# 02-Power.net
KiCad netlist of a schematic drawn in Altium Designer
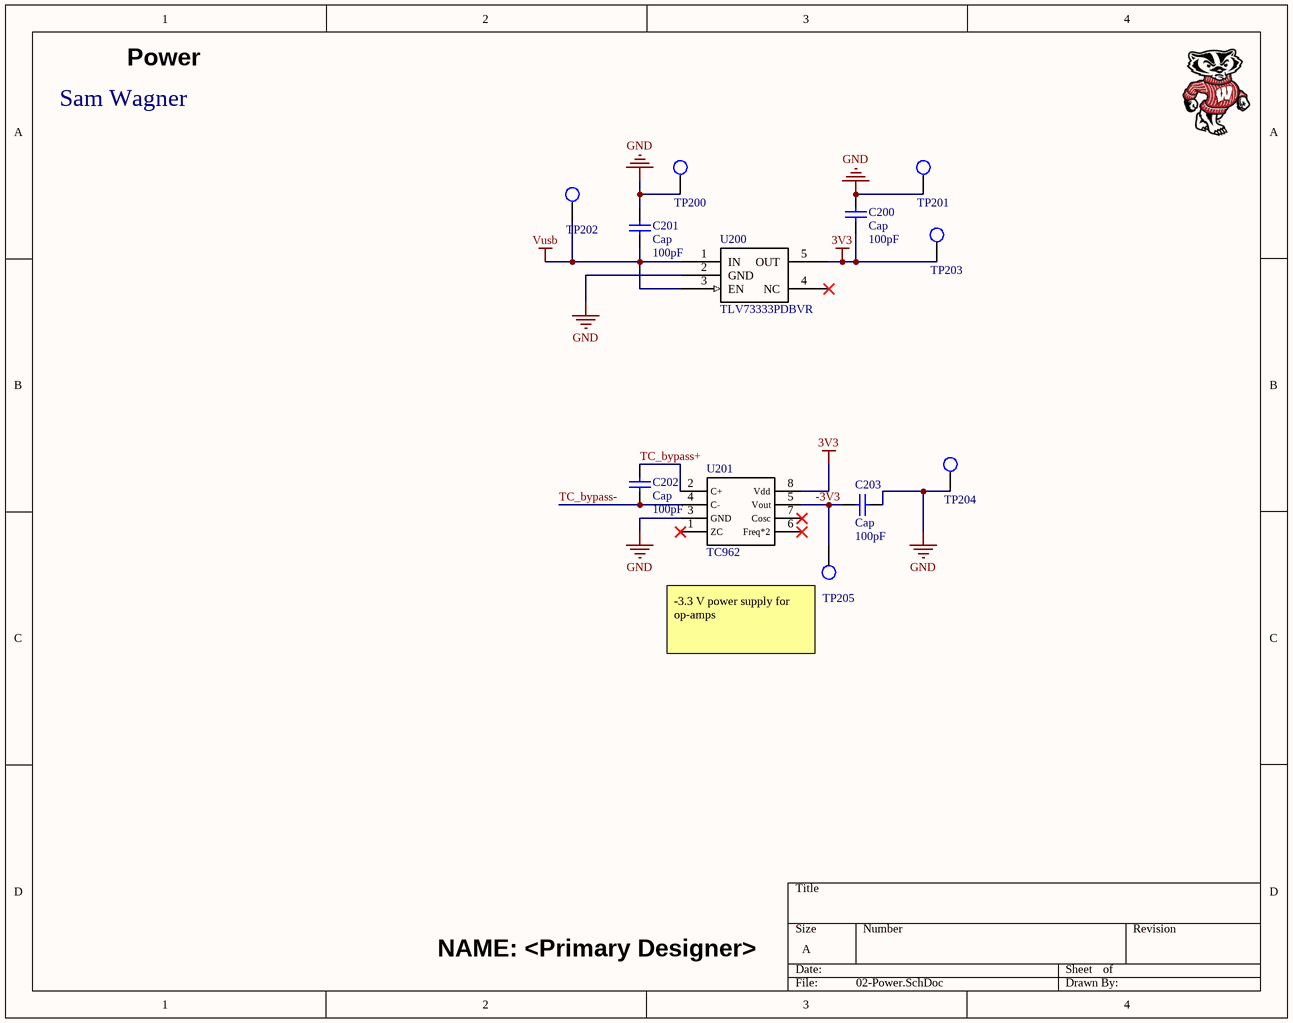
[diagram p0: 02-Power.SchDoc]

(export (version "E")
  (design (tool "Eeschema 10.0.6"))
  (components
    (comp (ref "C200")
      (value "Cap")
      (footprint "RAD-0.3")
      (description "Capacitor")
      (fields (field (name "ALTIUM_VALUE") "100pF") (field (name "PUBLISHER") "Altium Limited"))
      (libsource (lib "Miscellaneous Devices") (part "Cap"))
    )
    (comp (ref "C201")
      (value "Cap")
      (footprint "RAD-0.3")
      (description "Capacitor")
      (fields (field (name "ALTIUM_VALUE") "100pF") (field (name "PUBLISHER") "Altium Limited"))
      (libsource (lib "Miscellaneous Devices") (part "Cap"))
    )
    (comp (ref "C202")
      (value "Cap")
      (footprint "RAD-0.3")
      (description "Capacitor")
      (fields (field (name "ALTIUM_VALUE") "100pF") (field (name "PUBLISHER") "Altium Limited"))
      (libsource (lib "Miscellaneous Devices") (part "Cap"))
    )
    (comp (ref "C203")
      (value "Cap")
      (footprint "RAD-0.3")
      (description "Capacitor")
      (fields (field (name "ALTIUM_VALUE") "100pF") (field (name "PUBLISHER") "Altium Limited"))
      (libsource (lib "Miscellaneous Devices") (part "Cap"))
    )
    (comp (ref "TP200")
      (value "TP_1206")
      (footprint "TP-SMC-1206")
      (description "Test Point SMD 1206")
      (fields
        (field (name "MANUFACTURER") "TE Connectivity (Tyco Electronics)")
        (field (name "MANUFACTURER PART NUMBER") "1625854-1")
      )
      (libsource (lib "ece315-S20") (part "TP_1206"))
    )
    (comp (ref "TP201")
      (value "TP_1206")
      (footprint "TP-SMC-1206")
      (description "Test Point SMD 1206")
      (fields
        (field (name "MANUFACTURER") "TE Connectivity (Tyco Electronics)")
        (field (name "MANUFACTURER PART NUMBER") "1625854-1")
      )
      (libsource (lib "ece315-S20") (part "TP_1206"))
    )
    (comp (ref "TP202")
      (value "TP_1206")
      (footprint "TP-SMC-1206")
      (description "Test Point SMD 1206")
      (fields
        (field (name "MANUFACTURER") "TE Connectivity (Tyco Electronics)")
        (field (name "MANUFACTURER PART NUMBER") "1625854-1")
      )
      (libsource (lib "ece315-S20") (part "TP_1206"))
    )
    (comp (ref "TP203")
      (value "TP_1206")
      (footprint "TP-SMC-1206")
      (description "Test Point SMD 1206")
      (fields
        (field (name "MANUFACTURER") "TE Connectivity (Tyco Electronics)")
        (field (name "MANUFACTURER PART NUMBER") "1625854-1")
      )
      (libsource (lib "ece315-S20") (part "TP_1206"))
    )
    (comp (ref "TP204")
      (value "TP_1206")
      (footprint "TP-SMC-1206")
      (description "Test Point SMD 1206")
      (fields
        (field (name "MANUFACTURER") "TE Connectivity (Tyco Electronics)")
        (field (name "MANUFACTURER PART NUMBER") "1625854-1")
      )
      (libsource (lib "ece315-S20") (part "TP_1206"))
    )
    (comp (ref "TP205")
      (value "TP_1206")
      (footprint "TP-SMC-1206")
      (description "Test Point SMD 1206")
      (fields
        (field (name "MANUFACTURER") "TE Connectivity (Tyco Electronics)")
        (field (name "MANUFACTURER PART NUMBER") "1625854-1")
      )
      (libsource (lib "ece315-S20") (part "TP_1206"))
    )
    (comp (ref "U200")
      (value "IC-TLV733P")
      (footprint "IC_TLV73333")
      (description "IC REG LINEAR 3.3V 300MA SOT23-5")
      (fields
        (field (name "MANUFACTURER") "Texas Instruments")
        (field (name "MANUFACTOR PART NUMBER") "TLV73333PDBVR")
        (field (name "MANUFACTURER PART NUMBER") "TLV73333PDBVR")
      )
      (libsource (lib "ece315-S20") (part "IC-TLV733P"))
    )
    (comp (ref "U201")
      (value "TC962")
      (footprint "DIP8")
      (libsource (lib "Final_Project_Power") (part "TC962"))
    )
  )
  (nets
    (net (code "1") (name "/-3V3") (class "Default")
      (node (ref "C203") (pin "2") (pinfunction "2_2") (pintype "passive"))
      (node (ref "TP205") (pin "1") (pintype "passive"))
      (node (ref "U201") (pin "5") (pinfunction "Vout_5") (pintype "passive"))
    )
    (net (code "2") (name "/TC_bypass+") (class "Default")
      (node (ref "C202") (pin "1") (pinfunction "1_1") (pintype "passive"))
      (node (ref "U201") (pin "2") (pinfunction "C+_2") (pintype "passive"))
    )
    (net (code "3") (name "/TC_bypass-") (class "Default")
      (node (ref "C202") (pin "2") (pinfunction "2_2") (pintype "passive"))
      (node (ref "U201") (pin "4") (pinfunction "C-_4") (pintype "passive"))
    )
    (net (code "4") (name "3V3") (class "Default")
      (node (ref "C200") (pin "2") (pinfunction "2_2") (pintype "passive"))
      (node (ref "TP203") (pin "1") (pintype "passive"))
      (node (ref "U200") (pin "5") (pinfunction "OUT_5") (pintype "power_in"))
      (node (ref "U201") (pin "8") (pinfunction "Vdd_8") (pintype "passive"))
    )
    (net (code "5") (name "GND") (class "Default")
      (node (ref "C200") (pin "1") (pinfunction "1_1") (pintype "passive"))
      (node (ref "C201") (pin "2") (pinfunction "2_2") (pintype "passive"))
      (node (ref "C203") (pin "1") (pinfunction "1_1") (pintype "passive"))
      (node (ref "TP200") (pin "1") (pintype "passive"))
      (node (ref "TP201") (pin "1") (pintype "passive"))
      (node (ref "TP204") (pin "1") (pintype "passive"))
      (node (ref "U200") (pin "2") (pinfunction "GND_2") (pintype "power_in"))
      (node (ref "U201") (pin "3") (pinfunction "GND_3") (pintype "passive"))
    )
    (net (code "6") (name "Vusb") (class "Default")
      (node (ref "C201") (pin "1") (pinfunction "1_1") (pintype "passive"))
      (node (ref "TP202") (pin "1") (pintype "passive"))
      (node (ref "U200") (pin "1") (pinfunction "IN_1") (pintype "power_in"))
      (node (ref "U200") (pin "3") (pinfunction "EN_3") (pintype "input"))
    )
    (net (code "7") (name "unconnected-(U200-NC-Pad4)") (class "Default")
      (node (ref "U200") (pin "4") (pinfunction "NC_4") (pintype "passive+no_connect"))
    )
    (net (code "8") (name "unconnected-(U201-Cosc-Pad7)") (class "Default")
      (node (ref "U201") (pin "7") (pinfunction "Cosc_7") (pintype "passive+no_connect"))
    )
    (net (code "9") (name "unconnected-(U201-Freq*2-Pad6)") (class "Default")
      (node (ref "U201") (pin "6") (pinfunction "Freq*2_6") (pintype "passive+no_connect"))
    )
    (net (code "10") (name "unconnected-(U201-ZC-Pad1)") (class "Default")
      (node (ref "U201") (pin "1") (pinfunction "ZC_1") (pintype "passive+no_connect"))
    )
  )
)
